# stm32_board.net
KiCad netlist of a schematic drawn in Altium Designer
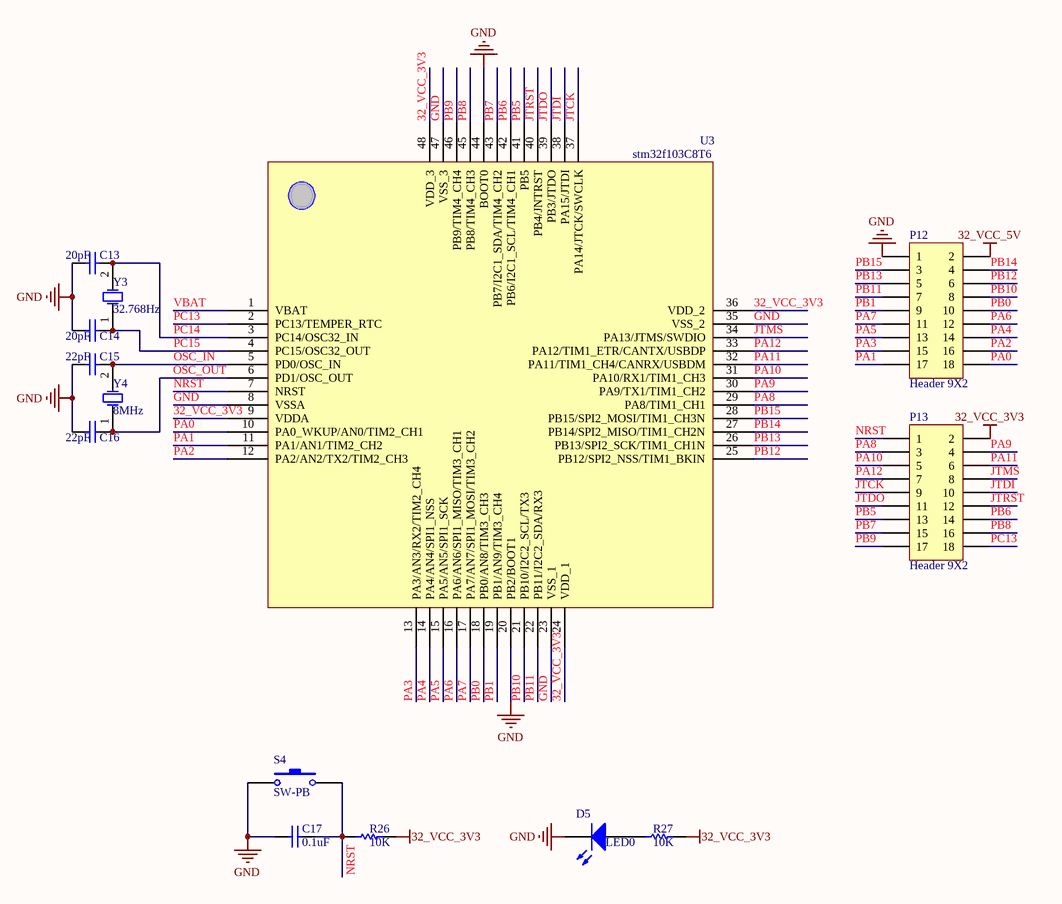
[diagram p0: stm32_board.SchDoc]

(export (version "E")
  (design (tool "Eeschema 10.0.6"))
  (components
    (comp (ref "C13")
      (value "20pF")
      (footprint "6-0805_N")
      (description "Capacitor")
      (fields (field (name "PUBLISHER") "Altium Limited"))
      (libsource (lib "Miscellaneous Devices") (part "Cap"))
    )
    (comp (ref "C14")
      (value "20pF")
      (footprint "6-0805_N")
      (description "Capacitor")
      (fields (field (name "PUBLISHER") "Altium Limited"))
      (libsource (lib "Miscellaneous Devices") (part "Cap"))
    )
    (comp (ref "C15")
      (value "22pF")
      (footprint "6-0805_N")
      (description "Capacitor")
      (fields (field (name "PUBLISHER") "Altium Limited"))
      (libsource (lib "Miscellaneous Devices") (part "Cap"))
    )
    (comp (ref "C16")
      (value "22pF")
      (footprint "6-0805_N")
      (description "Capacitor")
      (fields (field (name "PUBLISHER") "Altium Limited"))
      (libsource (lib "Miscellaneous Devices") (part "Cap"))
    )
    (comp (ref "C17")
      (value "0.1uF")
      (footprint "6-0805_N")
      (description "Capacitor")
      (fields (field (name "PUBLISHER") "Altium Limited"))
      (libsource (lib "Miscellaneous Devices") (part "Cap"))
    )
    (comp (ref "D5")
      (value "LED0")
      (footprint "LED")
      (description "Typical INFRARED GaAs LED")
      (fields (field (name "PUBLISHER") "Altium Limited"))
      (libsource (lib "Miscellaneous Devices") (part "LED0"))
    )
    (comp (ref "P12")
      (value "Header 9X2")
      (footprint "XDR2x9_S")
      (description "Header, 9-Pin, Dual row")
      (fields (field (name "PUBLISHER") "Altium Limited"))
      (libsource (lib "Miscellaneous Connectors") (part "Header 9X2"))
    )
    (comp (ref "P13")
      (value "Header 9X2")
      (footprint "XDR2x9_S")
      (description "Header, 9-Pin, Dual row")
      (fields (field (name "PUBLISHER") "Altium Limited"))
      (libsource (lib "Miscellaneous Connectors") (part "Header 9X2"))
    )
    (comp (ref "R26")
      (value "10K")
      (footprint "6-0805_N")
      (description "Resistor")
      (fields (field (name "PUBLISHER") "Altium Limited"))
      (libsource (lib "Miscellaneous Devices") (part "Res1"))
    )
    (comp (ref "R27")
      (value "10K")
      (footprint "6-0805_N")
      (description "Resistor")
      (fields (field (name "PUBLISHER") "Altium Limited"))
      (libsource (lib "Miscellaneous Devices") (part "Res1"))
    )
    (comp (ref "S4")
      (value "SW-PB")
      (footprint "SPST-2")
      (description "Switch")
      (fields (field (name "PUBLISHER") "Altium Limited"))
      (libsource (lib "Miscellaneous Devices") (part "SW-PB"))
    )
    (comp (ref "U3")
      (value "stm32f103C8T6")
      (footprint "LQFP48")
      (libsource (lib "BalanceCar") (part "stm32f103C8T6"))
    )
    (comp (ref "Y3")
      (value "32.768Hz")
      (footprint "HDR1X2")
      (description "Crystal Oscillator")
      (fields (field (name "PUBLISHER") "Altium Limited"))
      (libsource (lib "Miscellaneous Devices") (part "XTAL"))
    )
    (comp (ref "Y4")
      (value "8MHz")
      (footprint "HC-49S")
      (description "Crystal Oscillator")
      (fields (field (name "PUBLISHER") "Altium Limited"))
      (libsource (lib "Miscellaneous Devices") (part "XTAL"))
    )
  )
  (nets
    (net (code "1") (name "/JTCK") (class "Default")
      (node (ref "P13") (pin "9") (pinfunction "9_9") (pintype "passive"))
      (node (ref "U3") (pin "37") (pinfunction "PA14/JTCK/SWCLK_37") (pintype "passive"))
    )
    (net (code "2") (name "/JTDI") (class "Default")
      (node (ref "P13") (pin "10") (pinfunction "10_10") (pintype "passive"))
      (node (ref "U3") (pin "38") (pinfunction "PA15/JTDI_38") (pintype "passive"))
    )
    (net (code "3") (name "/JTDO") (class "Default")
      (node (ref "P13") (pin "11") (pinfunction "11_11") (pintype "passive"))
      (node (ref "U3") (pin "39") (pinfunction "PB3/JTDO_39") (pintype "passive"))
    )
    (net (code "4") (name "/JTMS") (class "Default")
      (node (ref "P13") (pin "8") (pinfunction "8_8") (pintype "passive"))
      (node (ref "U3") (pin "34") (pinfunction "PA13/JTMS/SWDIO_34") (pintype "passive"))
    )
    (net (code "5") (name "/JTRST") (class "Default")
      (node (ref "P13") (pin "12") (pinfunction "12_12") (pintype "passive"))
      (node (ref "U3") (pin "40") (pinfunction "PB4/JNTRST_40") (pintype "passive"))
    )
    (net (code "6") (name "/NRST") (class "Default")
      (node (ref "C17") (pin "2") (pinfunction "2_2") (pintype "passive"))
      (node (ref "P13") (pin "1") (pinfunction "1_1") (pintype "passive"))
      (node (ref "R26") (pin "1") (pinfunction "1_1") (pintype "passive"))
      (node (ref "S4") (pin "2") (pinfunction "2_2") (pintype "passive"))
      (node (ref "U3") (pin "7") (pinfunction "NRST_7") (pintype "passive"))
    )
    (net (code "7") (name "/OSC_IN") (class "Default")
      (node (ref "C15") (pin "2") (pinfunction "2_2") (pintype "passive"))
      (node (ref "U3") (pin "5") (pinfunction "PD0/OSC_IN_5") (pintype "passive"))
      (node (ref "Y4") (pin "2") (pinfunction "OSC2_2") (pintype "passive"))
    )
    (net (code "8") (name "/OSC_OUT") (class "Default")
      (node (ref "C16") (pin "2") (pinfunction "2_2") (pintype "passive"))
      (node (ref "U3") (pin "6") (pinfunction "PD1/OSC_OUT_6") (pintype "passive"))
      (node (ref "Y4") (pin "1") (pinfunction "OSC1_1") (pintype "passive"))
    )
    (net (code "9") (name "/PA0") (class "Default")
      (node (ref "P12") (pin "18") (pinfunction "18_18") (pintype "passive"))
      (node (ref "U3") (pin "10") (pinfunction "PA0_WKUP/AN0/TIM2_CH1_10") (pintype "passive"))
    )
    (net (code "10") (name "/PA1") (class "Default")
      (node (ref "P12") (pin "17") (pinfunction "17_17") (pintype "passive"))
      (node (ref "U3") (pin "11") (pinfunction "PA1/AN1/TIM2_CH2_11") (pintype "passive"))
    )
    (net (code "11") (name "/PA2") (class "Default")
      (node (ref "P12") (pin "16") (pinfunction "16_16") (pintype "passive"))
      (node (ref "U3") (pin "12") (pinfunction "PA2/AN2/TX2/TIM2_CH3_12") (pintype "passive"))
    )
    (net (code "12") (name "/PA3") (class "Default")
      (node (ref "P12") (pin "15") (pinfunction "15_15") (pintype "passive"))
      (node (ref "U3") (pin "13") (pinfunction "PA3/AN3/RX2/TIM2_CH4_13") (pintype "passive"))
    )
    (net (code "13") (name "/PA4") (class "Default")
      (node (ref "P12") (pin "14") (pinfunction "14_14") (pintype "passive"))
      (node (ref "U3") (pin "14") (pinfunction "PA4/AN4/SPI1_NSS_14") (pintype "passive"))
    )
    (net (code "14") (name "/PA5") (class "Default")
      (node (ref "P12") (pin "13") (pinfunction "13_13") (pintype "passive"))
      (node (ref "U3") (pin "15") (pinfunction "PA5/AN5/SPI1_SCK_15") (pintype "passive"))
    )
    (net (code "15") (name "/PA6") (class "Default")
      (node (ref "P12") (pin "12") (pinfunction "12_12") (pintype "passive"))
      (node (ref "U3") (pin "16") (pinfunction "PA6/AN6/SPI1_MISO/TIM3_CH1_16") (pintype "passive"))
    )
    (net (code "16") (name "/PA7") (class "Default")
      (node (ref "P12") (pin "11") (pinfunction "11_11") (pintype "passive"))
      (node (ref "U3") (pin "17") (pinfunction "PA7/AN7/SPI1_MOSI/TIM3_CH2_17") (pintype "passive"))
    )
    (net (code "17") (name "/PA8") (class "Default")
      (node (ref "P13") (pin "3") (pinfunction "3_3") (pintype "passive"))
      (node (ref "U3") (pin "29") (pinfunction "PA8/TIM1_CH1_29") (pintype "passive"))
    )
    (net (code "18") (name "/PA9") (class "Default")
      (node (ref "P13") (pin "4") (pinfunction "4_4") (pintype "passive"))
      (node (ref "U3") (pin "30") (pinfunction "PA9/TX1/TIM1_CH2_30") (pintype "passive"))
    )
    (net (code "19") (name "/PA10") (class "Default")
      (node (ref "P13") (pin "5") (pinfunction "5_5") (pintype "passive"))
      (node (ref "U3") (pin "31") (pinfunction "PA10/RX1/TIM1_CH3_31") (pintype "passive"))
    )
    (net (code "20") (name "/PA11") (class "Default")
      (node (ref "P13") (pin "6") (pinfunction "6_6") (pintype "passive"))
      (node (ref "U3") (pin "32") (pinfunction "PA11/TIM1_CH4/CANRX/USBDM_32") (pintype "passive"))
    )
    (net (code "21") (name "/PA12") (class "Default")
      (node (ref "P13") (pin "7") (pinfunction "7_7") (pintype "passive"))
      (node (ref "U3") (pin "33") (pinfunction "PA12/TIM1_ETR/CANTX/USBDP_33") (pintype "passive"))
    )
    (net (code "22") (name "/PB0") (class "Default")
      (node (ref "P12") (pin "10") (pinfunction "10_10") (pintype "passive"))
      (node (ref "U3") (pin "18") (pinfunction "PB0/AN8/TIM3_CH3_18") (pintype "passive"))
    )
    (net (code "23") (name "/PB1") (class "Default")
      (node (ref "P12") (pin "9") (pinfunction "9_9") (pintype "passive"))
      (node (ref "U3") (pin "19") (pinfunction "PB1/AN9/TIM3_CH4_19") (pintype "passive"))
    )
    (net (code "24") (name "/PB5") (class "Default")
      (node (ref "P13") (pin "13") (pinfunction "13_13") (pintype "passive"))
      (node (ref "U3") (pin "41") (pinfunction "PB5_41") (pintype "passive"))
    )
    (net (code "25") (name "/PB6") (class "Default")
      (node (ref "P13") (pin "14") (pinfunction "14_14") (pintype "passive"))
      (node (ref "U3") (pin "42") (pinfunction "PB6/I2C1_SCL/TIM4_CH1_42") (pintype "passive"))
    )
    (net (code "26") (name "/PB7") (class "Default")
      (node (ref "P13") (pin "15") (pinfunction "15_15") (pintype "passive"))
      (node (ref "U3") (pin "43") (pinfunction "PB7/I2C1_SDA/TIM4_CH2_43") (pintype "passive"))
    )
    (net (code "27") (name "/PB8") (class "Default")
      (node (ref "P13") (pin "16") (pinfunction "16_16") (pintype "passive"))
      (node (ref "U3") (pin "45") (pinfunction "PB8/TIM4_CH3_45") (pintype "passive"))
    )
    (net (code "28") (name "/PB9") (class "Default")
      (node (ref "P13") (pin "17") (pinfunction "17_17") (pintype "passive"))
      (node (ref "U3") (pin "46") (pinfunction "PB9/TIM4_CH4_46") (pintype "passive"))
    )
    (net (code "29") (name "/PB10") (class "Default")
      (node (ref "P12") (pin "8") (pinfunction "8_8") (pintype "passive"))
      (node (ref "U3") (pin "21") (pinfunction "PB10/I2C2_SCL/TX3_21") (pintype "passive"))
    )
    (net (code "30") (name "/PB11") (class "Default")
      (node (ref "P12") (pin "7") (pinfunction "7_7") (pintype "passive"))
      (node (ref "U3") (pin "22") (pinfunction "PB11/I2C2_SDA/RX3_22") (pintype "passive"))
    )
    (net (code "31") (name "/PB12") (class "Default")
      (node (ref "P12") (pin "6") (pinfunction "6_6") (pintype "passive"))
      (node (ref "U3") (pin "25") (pinfunction "PB12/SPI2_NSS/TIM1_BKIN_25") (pintype "passive"))
    )
    (net (code "32") (name "/PB13") (class "Default")
      (node (ref "P12") (pin "5") (pinfunction "5_5") (pintype "passive"))
      (node (ref "U3") (pin "26") (pinfunction "PB13/SPI2_SCK/TIM1_CH1N_26") (pintype "passive"))
    )
    (net (code "33") (name "/PB14") (class "Default")
      (node (ref "P12") (pin "4") (pinfunction "4_4") (pintype "passive"))
      (node (ref "U3") (pin "27") (pinfunction "PB14/SPI2_MISO/TIM1_CH2N_27") (pintype "passive"))
    )
    (net (code "34") (name "/PB15") (class "Default")
      (node (ref "P12") (pin "3") (pinfunction "3_3") (pintype "passive"))
      (node (ref "U3") (pin "28") (pinfunction "PB15/SPI2_MOSI/TIM1_CH3N_28") (pintype "passive"))
    )
    (net (code "35") (name "/PC13") (class "Default")
      (node (ref "P13") (pin "18") (pinfunction "18_18") (pintype "passive"))
      (node (ref "U3") (pin "2") (pinfunction "PC13/TEMPER_RTC_2") (pintype "passive"))
    )
    (net (code "36") (name "/PC14") (class "Default")
      (node (ref "C13") (pin "2") (pinfunction "2_2") (pintype "passive"))
      (node (ref "U3") (pin "3") (pinfunction "PC14/OSC32_IN_3") (pintype "passive"))
      (node (ref "Y3") (pin "2") (pinfunction "OSC2_2") (pintype "passive"))
    )
    (net (code "37") (name "/PC15") (class "Default")
      (node (ref "C14") (pin "2") (pinfunction "2_2") (pintype "passive"))
      (node (ref "U3") (pin "4") (pinfunction "PC15/OSC32_OUT_4") (pintype "passive"))
      (node (ref "Y3") (pin "1") (pinfunction "OSC1_1") (pintype "passive"))
    )
    (net (code "38") (name "/VBAT") (class "Default")
      (node (ref "U3") (pin "1") (pinfunction "VBAT_1") (pintype "passive"))
    )
    (net (code "39") (name "32_VCC_3V3") (class "Default")
      (node (ref "P13") (pin "2") (pinfunction "2_2") (pintype "passive"))
      (node (ref "R26") (pin "2") (pinfunction "2_2") (pintype "passive"))
      (node (ref "R27") (pin "2") (pinfunction "2_2") (pintype "passive"))
      (node (ref "U3") (pin "24") (pinfunction "VDD_1_24") (pintype "passive"))
      (node (ref "U3") (pin "36") (pinfunction "VDD_2_36") (pintype "passive"))
      (node (ref "U3") (pin "48") (pinfunction "VDD_3_48") (pintype "passive"))
      (node (ref "U3") (pin "9") (pinfunction "VDDA_9") (pintype "passive"))
    )
    (net (code "40") (name "32_VCC_5V") (class "Default")
      (node (ref "P12") (pin "2") (pinfunction "2_2") (pintype "passive"))
    )
    (net (code "41") (name "GND") (class "Default")
      (node (ref "C13") (pin "1") (pinfunction "1_1") (pintype "passive"))
      (node (ref "C14") (pin "1") (pinfunction "1_1") (pintype "passive"))
      (node (ref "C15") (pin "1") (pinfunction "1_1") (pintype "passive"))
      (node (ref "C16") (pin "1") (pinfunction "1_1") (pintype "passive"))
      (node (ref "C17") (pin "1") (pinfunction "1_1") (pintype "passive"))
      (node (ref "D5") (pin "2") (pinfunction "K_2") (pintype "passive"))
      (node (ref "P12") (pin "1") (pinfunction "1_1") (pintype "passive"))
      (node (ref "S4") (pin "1") (pinfunction "1_1") (pintype "passive"))
      (node (ref "U3") (pin "20") (pinfunction "PB2/BOOT1_20") (pintype "passive"))
      (node (ref "U3") (pin "23") (pinfunction "VSS_1_23") (pintype "passive"))
      (node (ref "U3") (pin "35") (pinfunction "VSS_2_35") (pintype "passive"))
      (node (ref "U3") (pin "44") (pinfunction "BOOT0_44") (pintype "passive"))
      (node (ref "U3") (pin "47") (pinfunction "VSS_3_47") (pintype "passive"))
      (node (ref "U3") (pin "8") (pinfunction "VSSA_8") (pintype "passive"))
    )
    (net (code "42") (name "Net-(D5-A)") (class "Default")
      (node (ref "D5") (pin "1") (pinfunction "A_1") (pintype "passive"))
      (node (ref "R27") (pin "1") (pinfunction "1_1") (pintype "passive"))
    )
  )
)
